# SCH_Elektrisch_Schema_B_2022-10-21.net
KiCad netlist of a schematic drawn in EasyEDA
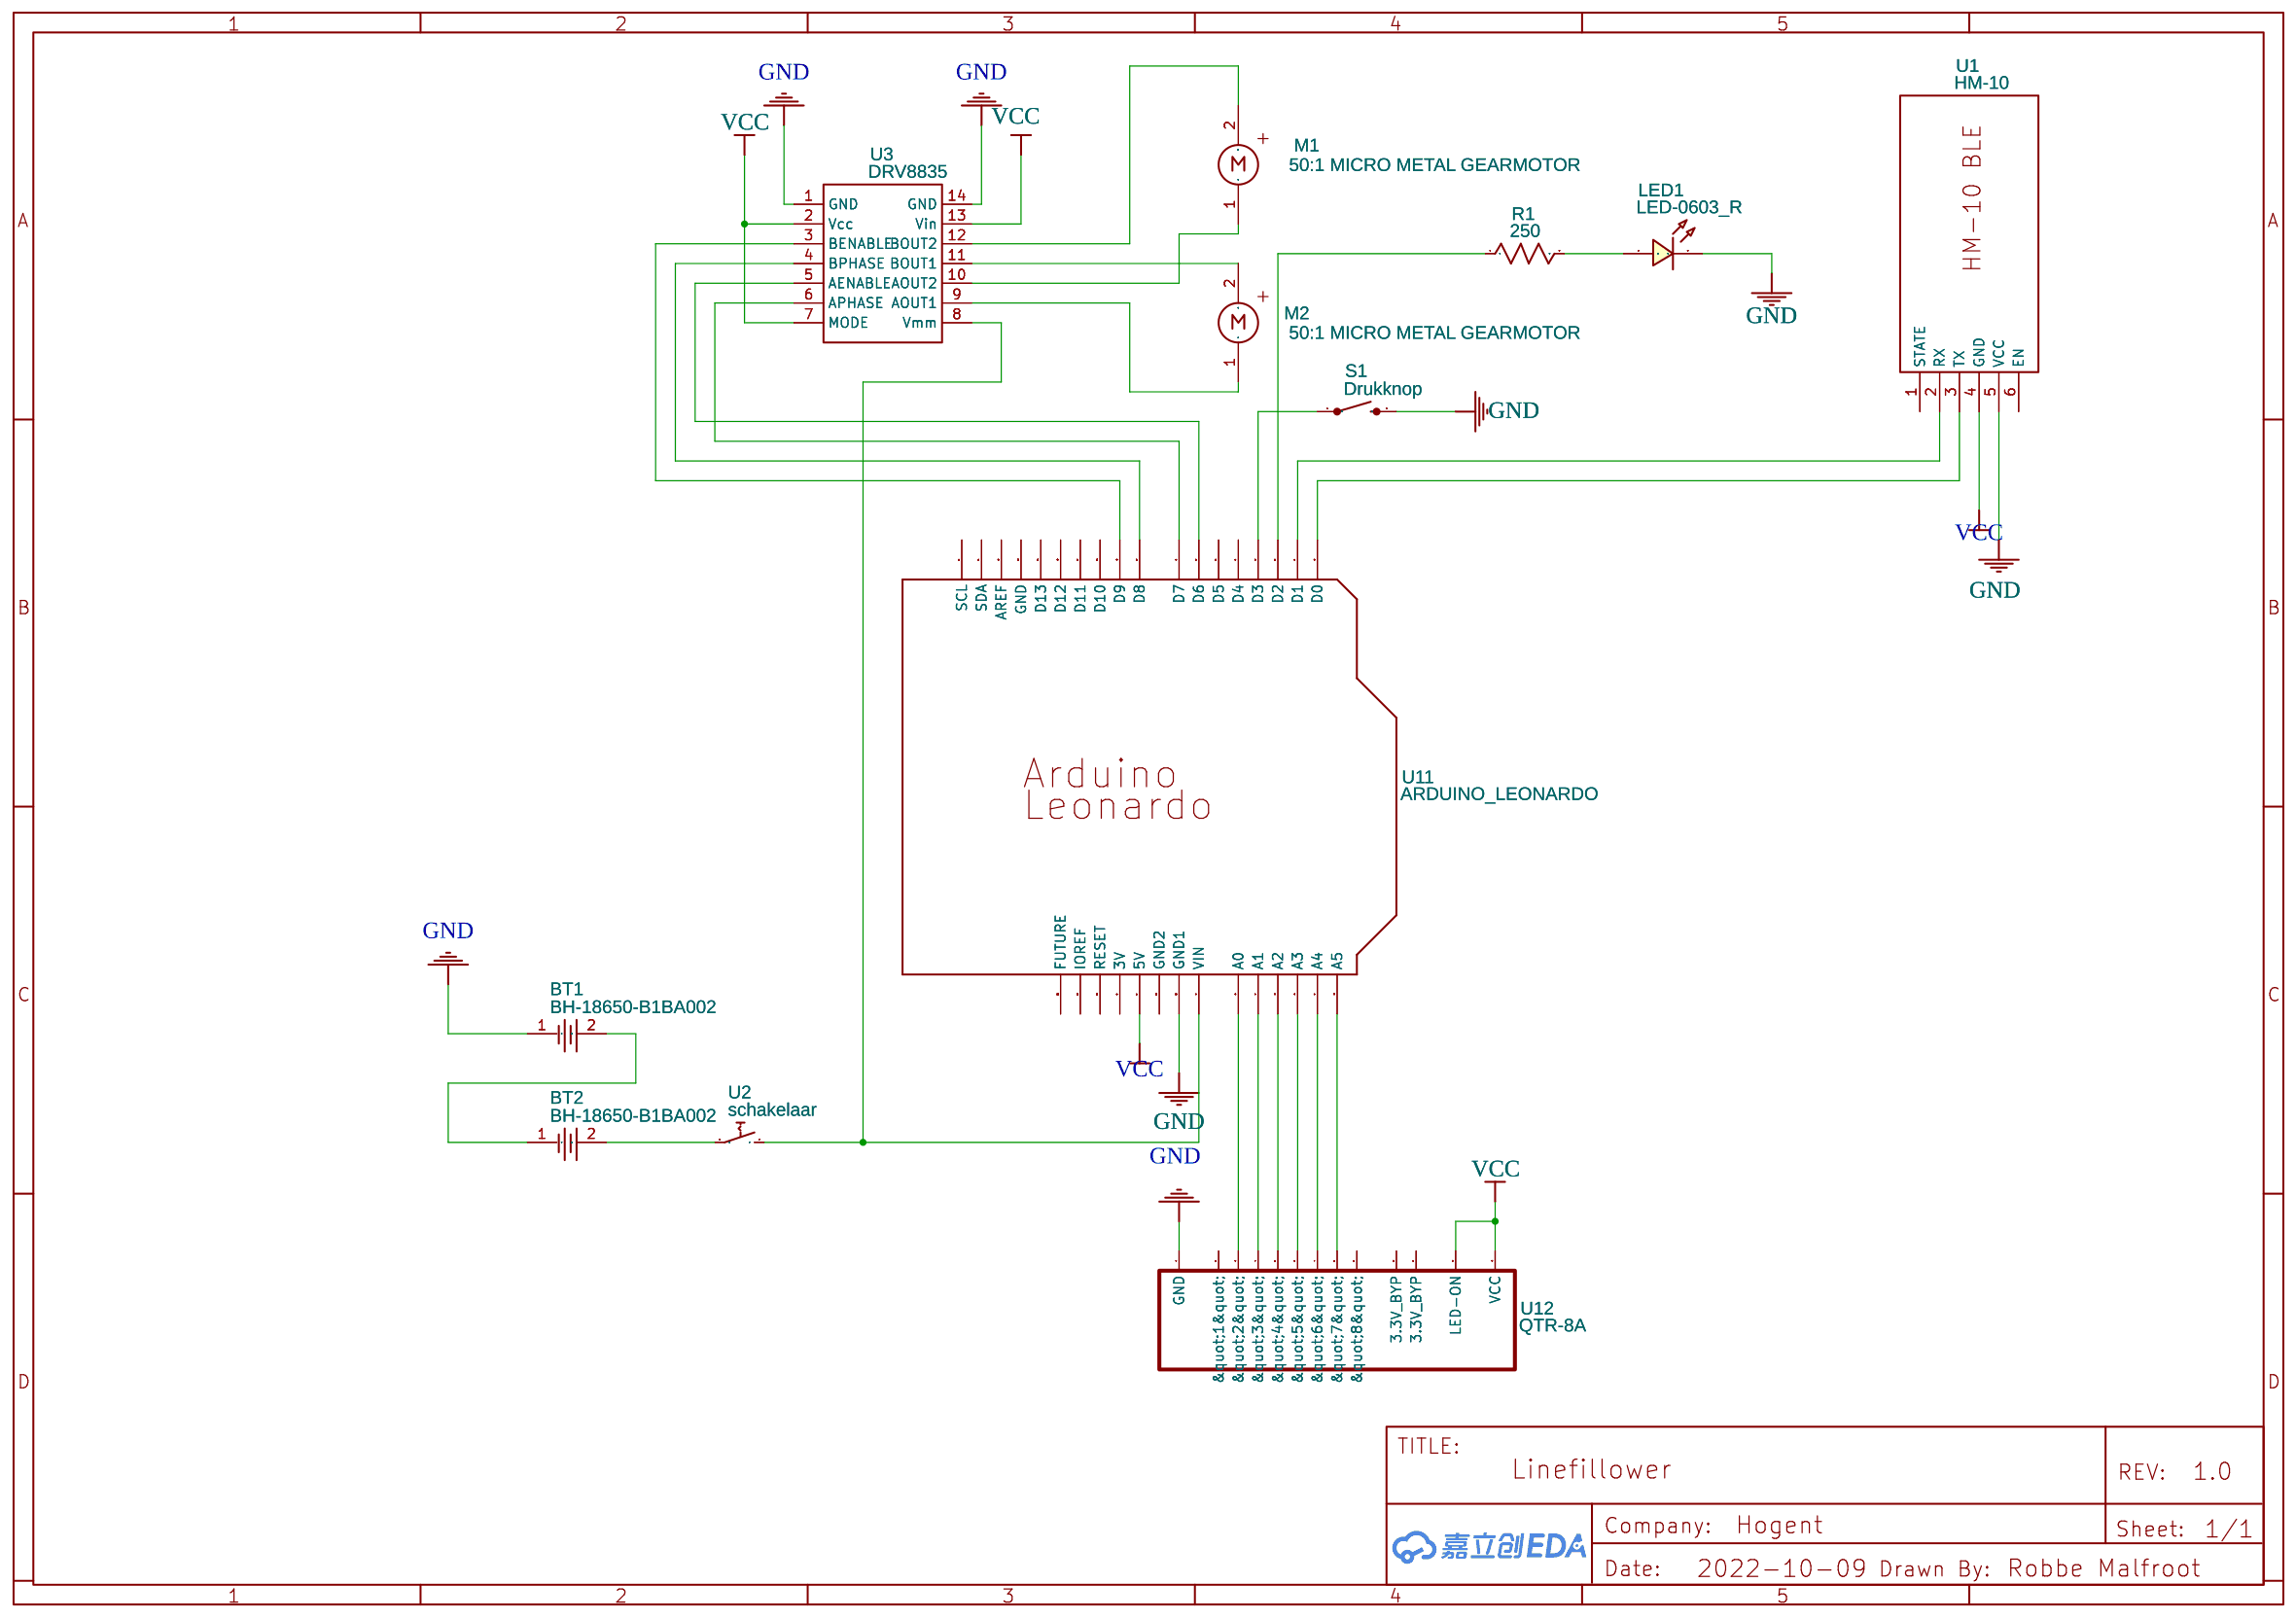
[diagram p0: schematic sheet]

(export (version "E")
  (design (tool "Eeschema 10.0.6"))
  (components
    (comp (ref "BT1")
      (value "BH-18650-B1BA002")
      (fields (field (name "BOM_Supplier Part") "C2988620"))
      (libsource (lib "") (part "BH-18650-B1BA002"))
    )
    (comp (ref "BT2")
      (value "BH-18650-B1BA002")
      (fields (field (name "BOM_Supplier Part") "C2988620"))
      (libsource (lib "") (part "BH-18650-B1BA002"))
    )
    (comp (ref "LED1")
      (value "LED-0603_R")
      (fields
        (field (name "BOM_Manufacturer Part") "19-217/R6C-AL1M2VY/3T")
        (field (name "BOM_Supplier Part") "C72044")
      )
      (libsource (lib "") (part "LED-0603_R"))
    )
    (comp (ref "M1")
      (value "50:1 MICRO METAL GEARMOTOR")
      (fields
        (field (name "BOM_Manufacturer Part") "10:1 Micro Metal Gearmotor HPCB 6V with Extended Motor Shaft")
        (field (name "BOM_Supplier Part") "3071")
      )
      (libsource (lib "") (part "10{colon}1 MICRO METAL GEARMOTOR eskere"))
    )
    (comp (ref "M2")
      (value "50:1 MICRO METAL GEARMOTOR")
      (fields
        (field (name "BOM_Manufacturer Part") "10:1 Micro Metal Gearmotor HPCB 6V with Extended Motor Shaft")
        (field (name "BOM_Supplier Part") "3071")
      )
      (libsource (lib "") (part "10{colon}1 MICRO METAL GEARMOTOR eskere"))
    )
    (comp (ref "R1") (value "250") (libsource (lib "") (part "R_0603_US")))
    (comp (ref "S1") (value "Drukknop") (libsource (lib "") (part "Drukknop")))
    (comp (ref "U1") (value "HM-10") (libsource (lib "") (part "HM-10")))
    (comp (ref "U2") (value "schakelaar") (libsource (lib "") (part "schakelaar")))
    (comp (ref "U3") (value "DRV8835") (libsource (lib "") (part "DRV8835")))
    (comp (ref "U11") (value "ARDUINO_LEONARDO") (libsource (lib "") (part "ARDUINO_LEONARDO")))
    (comp (ref "U12")
      (value "QTR-8A")
      (fields (field (name "BOM_Supplier Part") "960"))
      (libsource (lib "") (part "QTR-8A"))
    )
  )
  (nets
    (net (code "1") (name "GND") (class "Default")
      (node (ref "BT1") (pin "1") (pinfunction "1_1") (pintype "input"))
      (node (ref "LED1") (pin "2") (pinfunction "2_2") (pintype "unspecified"))
      (node (ref "S1") (pin "2") (pinfunction "2_2") (pintype "unspecified"))
      (node (ref "U1") (pin "5") (pinfunction "VCC_5") (pintype "unspecified"))
      (node (ref "U11") (pin "GND$3") (pinfunction "GND1_GND$3") (pintype "passive"))
      (node (ref "U12") (pin "1") (pinfunction "GND_1") (pintype "unspecified"))
      (node (ref "U3") (pin "1") (pinfunction "GND_1") (pintype "unspecified"))
      (node (ref "U3") (pin "14") (pinfunction "GND_14") (pintype "unspecified"))
    )
    (net (code "2") (name "Net-(BT1-Pad2)") (class "Default")
      (node (ref "BT1") (pin "2") (pinfunction "2_2") (pintype "input"))
      (node (ref "BT2") (pin "1") (pinfunction "1_1") (pintype "input"))
    )
    (net (code "3") (name "Net-(BT2-Pad2)") (class "Default")
      (node (ref "BT2") (pin "2") (pinfunction "2_2") (pintype "input"))
      (node (ref "U2") (pin "2") (pinfunction "2_2") (pintype "unspecified"))
    )
    (net (code "4") (name "Net-(LED1-Pad1)") (class "Default")
      (node (ref "LED1") (pin "1") (pinfunction "1_1") (pintype "unspecified"))
      (node (ref "R1") (pin "2") (pinfunction "2_2") (pintype "unspecified"))
    )
    (net (code "5") (name "Net-(R1-Pad1)") (class "Default")
      (node (ref "R1") (pin "1") (pinfunction "1_1") (pintype "unspecified"))
      (node (ref "U11") (pin "D2") (pinfunction "D2_D2") (pintype "unspecified"))
    )
    (net (code "6") (name "Net-(S1-Pad1)") (class "Default")
      (node (ref "S1") (pin "1") (pinfunction "1_1") (pintype "unspecified"))
      (node (ref "U11") (pin "D3") (pinfunction "D3_D3") (pintype "unspecified"))
    )
    (net (code "7") (name "Net-(U1-RX)") (class "Default")
      (node (ref "U1") (pin "2") (pinfunction "RX_2") (pintype "unspecified"))
      (node (ref "U11") (pin "D1") (pinfunction "D1_D1") (pintype "unspecified"))
    )
    (net (code "8") (name "Net-(U1-TX)") (class "Default")
      (node (ref "U1") (pin "3") (pinfunction "TX_3") (pintype "unspecified"))
      (node (ref "U11") (pin "D0") (pinfunction "D0_D0") (pintype "unspecified"))
    )
    (net (code "9") (name "Net-(U3-AENABLE)") (class "Default")
      (node (ref "U11") (pin "D6") (pinfunction "D6_D6") (pintype "unspecified"))
      (node (ref "U3") (pin "5") (pinfunction "AENABLE_5") (pintype "unspecified"))
    )
    (net (code "10") (name "Net-(U3-AOUT1)") (class "Default")
      (node (ref "M2") (pin "1") (pinfunction "1_1") (pintype "unspecified"))
      (node (ref "U3") (pin "9") (pinfunction "AOUT1_9") (pintype "unspecified"))
    )
    (net (code "11") (name "Net-(U3-AOUT2)") (class "Default")
      (node (ref "M1") (pin "1") (pinfunction "1_1") (pintype "unspecified"))
      (node (ref "U3") (pin "10") (pinfunction "AOUT2_10") (pintype "unspecified"))
    )
    (net (code "12") (name "Net-(U3-APHASE)") (class "Default")
      (node (ref "U11") (pin "D7") (pinfunction "D7_D7") (pintype "unspecified"))
      (node (ref "U3") (pin "6") (pinfunction "APHASE_6") (pintype "unspecified"))
    )
    (net (code "13") (name "Net-(U3-BENABLE)") (class "Default")
      (node (ref "U11") (pin "D9") (pinfunction "D9_D9") (pintype "unspecified"))
      (node (ref "U3") (pin "3") (pinfunction "BENABLE_3") (pintype "unspecified"))
    )
    (net (code "14") (name "Net-(U3-BOUT1)") (class "Default")
      (node (ref "M2") (pin "2") (pinfunction "2_2") (pintype "unspecified"))
      (node (ref "U3") (pin "11") (pinfunction "BOUT1_11") (pintype "unspecified"))
    )
    (net (code "15") (name "Net-(U3-BOUT2)") (class "Default")
      (node (ref "M1") (pin "2") (pinfunction "2_2") (pintype "unspecified"))
      (node (ref "U3") (pin "12") (pinfunction "BOUT2_12") (pintype "unspecified"))
    )
    (net (code "16") (name "Net-(U3-BPHASE)") (class "Default")
      (node (ref "U11") (pin "D8") (pinfunction "D8_D8") (pintype "unspecified"))
      (node (ref "U3") (pin "4") (pinfunction "BPHASE_4") (pintype "unspecified"))
    )
    (net (code "17") (name "Net-(U3-Vmm)") (class "Default")
      (node (ref "U11") (pin "VIN") (pinfunction "VIN_VIN") (pintype "passive"))
      (node (ref "U2") (pin "1") (pinfunction "1_1") (pintype "unspecified"))
      (node (ref "U3") (pin "8") (pinfunction "Vmm_8") (pintype "unspecified"))
    )
    (net (code "18") (name "Net-(U12-&quot;2&quot;)") (class "Default")
      (node (ref "U11") (pin "A0") (pinfunction "A0_A0") (pintype "unspecified"))
      (node (ref "U12") (pin "3") (pinfunction "&quot;2&quot;_3") (pintype "unspecified"))
    )
    (net (code "19") (name "Net-(U12-&quot;3&quot;)") (class "Default")
      (node (ref "U11") (pin "A1") (pinfunction "A1_A1") (pintype "unspecified"))
      (node (ref "U12") (pin "4") (pinfunction "&quot;3&quot;_4") (pintype "unspecified"))
    )
    (net (code "20") (name "Net-(U12-&quot;4&quot;)") (class "Default")
      (node (ref "U11") (pin "A2") (pinfunction "A2_A2") (pintype "unspecified"))
      (node (ref "U12") (pin "5") (pinfunction "&quot;4&quot;_5") (pintype "unspecified"))
    )
    (net (code "21") (name "Net-(U12-&quot;5&quot;)") (class "Default")
      (node (ref "U11") (pin "A3") (pinfunction "A3_A3") (pintype "unspecified"))
      (node (ref "U12") (pin "6") (pinfunction "&quot;5&quot;_6") (pintype "unspecified"))
    )
    (net (code "22") (name "Net-(U12-&quot;6&quot;)") (class "Default")
      (node (ref "U11") (pin "A4") (pinfunction "A4_A4") (pintype "unspecified"))
      (node (ref "U12") (pin "7") (pinfunction "&quot;6&quot;_7") (pintype "unspecified"))
    )
    (net (code "23") (name "Net-(U12-&quot;7&quot;)") (class "Default")
      (node (ref "U11") (pin "A5") (pinfunction "A5_A5") (pintype "unspecified"))
      (node (ref "U12") (pin "8") (pinfunction "&quot;7&quot;_8") (pintype "unspecified"))
    )
    (net (code "24") (name "VCC") (class "Default")
      (node (ref "U1") (pin "4") (pinfunction "GND_4") (pintype "unspecified"))
      (node (ref "U11") (pin "5V") (pinfunction "5V_5V") (pintype "passive"))
      (node (ref "U12") (pin "12") (pinfunction "LED-ON_12") (pintype "unspecified"))
      (node (ref "U3") (pin "13") (pinfunction "Vin_13") (pintype "unspecified"))
      (node (ref "U3") (pin "2") (pinfunction "Vcc_2") (pintype "unspecified"))
      (node (ref "U3") (pin "7") (pinfunction "MODE_7") (pintype "unspecified"))
    )
    (net (code "25") (name "unconnected-(U1-EN-Pad6)") (class "Default")
      (node (ref "U1") (pin "6") (pinfunction "EN_6") (pintype "unspecified"))
    )
    (net (code "26") (name "unconnected-(U1-STATE-Pad1)") (class "Default")
      (node (ref "U1") (pin "1") (pinfunction "STATE_1") (pintype "unspecified"))
    )
    (net (code "27") (name "unconnected-(U11-FUTURE-PadRESERVED)") (class "Default")
      (node (ref "U11") (pin "RESERVED") (pinfunction "FUTURE_RESERVED") (pintype "unspecified"))
    )
    (net (code "28") (name "unconnected-(U11-GND2-PadGND$2)") (class "Default")
      (node (ref "U11") (pin "GND$2") (pinfunction "GND2_GND$2") (pintype "passive"))
    )
    (net (code "29") (name "unconnected-(U11-Pad3V)") (class "Default")
      (node (ref "U11") (pin "3V") (pinfunction "3V_3V") (pintype "passive"))
    )
    (net (code "30") (name "unconnected-(U11-PadAREF)") (class "Default")
      (node (ref "U11") (pin "AREF") (pinfunction "AREF_AREF") (pintype "unspecified"))
    )
    (net (code "31") (name "unconnected-(U11-PadD4)") (class "Default")
      (node (ref "U11") (pin "D4") (pinfunction "D4_D4") (pintype "unspecified"))
    )
    (net (code "32") (name "unconnected-(U11-PadD5)") (class "Default")
      (node (ref "U11") (pin "D5") (pinfunction "D5_D5") (pintype "unspecified"))
    )
    (net (code "33") (name "unconnected-(U11-PadD10)") (class "Default")
      (node (ref "U11") (pin "D10") (pinfunction "D10_D10") (pintype "unspecified"))
    )
    (net (code "34") (name "unconnected-(U11-PadD11)") (class "Default")
      (node (ref "U11") (pin "D11") (pinfunction "D11_D11") (pintype "unspecified"))
    )
    (net (code "35") (name "unconnected-(U11-PadD12)") (class "Default")
      (node (ref "U11") (pin "D12") (pinfunction "D12_D12") (pintype "unspecified"))
    )
    (net (code "36") (name "unconnected-(U11-PadD13)") (class "Default")
      (node (ref "U11") (pin "D13") (pinfunction "D13_D13") (pintype "unspecified"))
    )
    (net (code "37") (name "unconnected-(U11-PadGND)") (class "Default")
      (node (ref "U11") (pin "GND") (pinfunction "GND_GND") (pintype "passive"))
    )
    (net (code "38") (name "unconnected-(U11-PadIOREF)") (class "Default")
      (node (ref "U11") (pin "IOREF") (pinfunction "IOREF_IOREF") (pintype "unspecified"))
    )
    (net (code "39") (name "unconnected-(U11-PadRESET)") (class "Default")
      (node (ref "U11") (pin "RESET") (pinfunction "RESET_RESET") (pintype "unspecified"))
    )
    (net (code "40") (name "unconnected-(U11-PadSCL)") (class "Default")
      (node (ref "U11") (pin "SCL") (pinfunction "SCL_SCL") (pintype "unspecified"))
    )
    (net (code "41") (name "unconnected-(U11-PadSDA)") (class "Default")
      (node (ref "U11") (pin "SDA") (pinfunction "SDA_SDA") (pintype "unspecified"))
    )
    (net (code "42") (name "unconnected-(U12-&quot;1&quot;-Pad2)") (class "Default")
      (node (ref "U12") (pin "2") (pinfunction "&quot;1&quot;_2") (pintype "unspecified"))
    )
    (net (code "43") (name "unconnected-(U12-&quot;8&quot;-Pad9)") (class "Default")
      (node (ref "U12") (pin "9") (pinfunction "&quot;8&quot;_9") (pintype "unspecified"))
    )
    (net (code "44") (name "unconnected-(U12-3.3V_BYP-Pad10)") (class "Default")
      (node (ref "U12") (pin "10") (pinfunction "3.3V_BYP_10") (pintype "unspecified"))
    )
    (net (code "45") (name "unconnected-(U12-3.3V_BYP-Pad11)") (class "Default")
      (node (ref "U12") (pin "11") (pinfunction "3.3V_BYP_11") (pintype "unspecified"))
    )
  )
)
